# POWER_GEN.net
KiCad netlist of a schematic drawn in Altium Designer
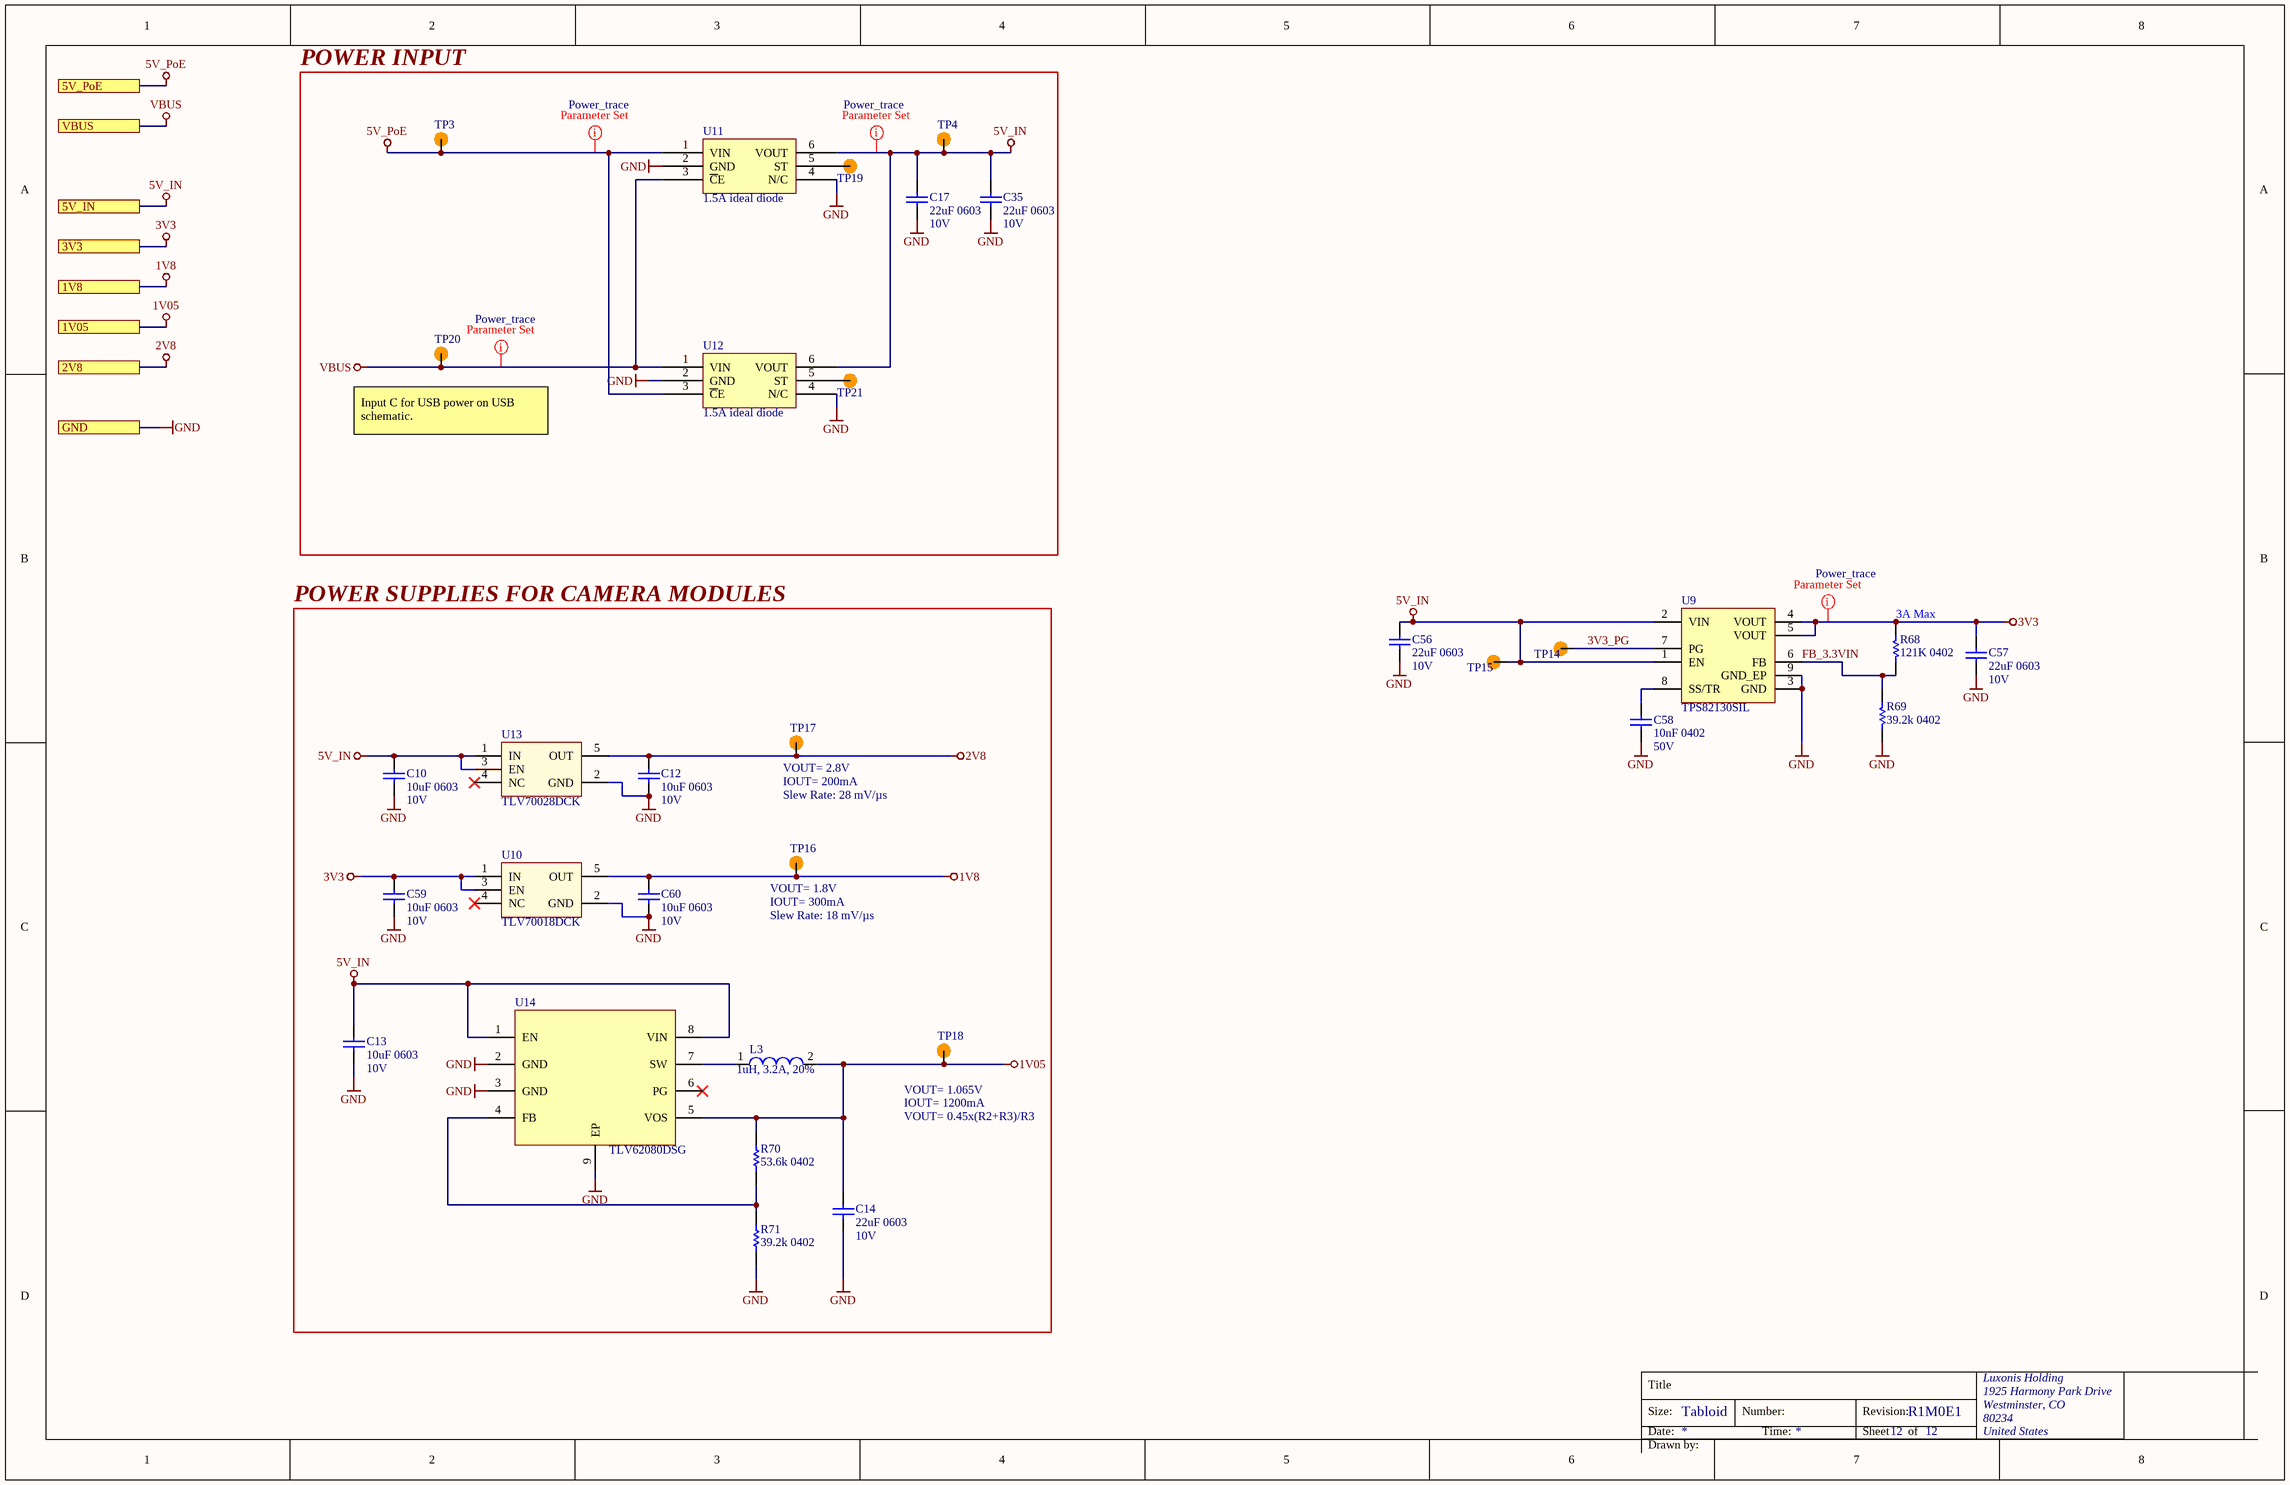
[diagram p0: POWER_GEN.SchDoc]

(export (version "E")
  (design (tool "Eeschema 10.0.6"))
  (components
    (comp (ref "C10")
      (value "10uF 0603")
      (footprint "CAP_Altium_Vault_Generic:CAPC0603(1608)100_N")
      (description "CAP CER 10UF 10V X5R 0603 20%")
      (fields (field (name "TOLERANCE") "20%") (field (name "VOLTAGE RATING") "10V"))
      (libsource (lib "LuxonisMaster") (part "GRM188R61A106ME69D"))
    )
    (comp (ref "C12")
      (value "10uF 0603")
      (footprint "CAP_Altium_Vault_Generic:CAPC0603(1608)100_N")
      (description "CAP CER 10UF 10V X5R 0603 20%")
      (fields (field (name "TOLERANCE") "20%") (field (name "VOLTAGE RATING") "10V"))
      (libsource (lib "LuxonisMaster") (part "GRM188R61A106ME69D"))
    )
    (comp (ref "C13")
      (value "10uF 0603")
      (footprint "CAP_Altium_Vault_Generic:CAPC0603(1608)100_L")
      (description "CAP CER 10UF 10V X5R 0603 20%")
      (fields (field (name "TOLERANCE") "20%") (field (name "VOLTAGE RATING") "10V"))
      (libsource (lib "LuxonisMaster") (part "GRM188R61A106ME69D"))
    )
    (comp (ref "C14")
      (value "22uF 0603")
      (footprint "CAP_Altium_Vault_Generic:CAPC0603(1608)100_L")
      (description "CAP CER 22UF 10V X5R 0603 20%")
      (fields (field (name "TOLERANCE") "20%") (field (name "VOLTAGE RATING") "10V"))
      (libsource (lib "LuxonisMaster") (part "GRM188R61A226ME15D"))
    )
    (comp (ref "C17")
      (value "22uF 0603")
      (footprint "CAP_Altium_Vault_Generic:CAPC0603(1608)100_L")
      (description "CAP CER 22UF 10V X5R 0603 20%")
      (fields (field (name "TOLERANCE") "20%") (field (name "VOLTAGE RATING") "10V"))
      (libsource (lib "LuxonisMaster") (part "GRM188R61A226ME15D"))
    )
    (comp (ref "C35")
      (value "22uF 0603")
      (footprint "CAP_Altium_Vault_Generic:CAPC0603(1608)100_L")
      (description "CAP CER 22UF 10V X5R 0603 20%")
      (fields (field (name "TOLERANCE") "20%") (field (name "VOLTAGE RATING") "10V"))
      (libsource (lib "LuxonisMaster") (part "GRM188R61A226ME15D"))
    )
    (comp (ref "C56")
      (value "22uF 0603")
      (footprint "CAP_Altium_Vault_Generic:CAPC0603(1608)100_N")
      (description "CAP CER 22UF 10V X5R 0603 20%")
      (fields (field (name "TOLERANCE") "20%") (field (name "VOLTAGE RATING") "10V"))
      (libsource (lib "LuxonisMaster") (part "GRM188R61A226ME15D"))
    )
    (comp (ref "C57")
      (value "22uF 0603")
      (footprint "CAP_Altium_Vault_Generic:CAPC0603(1608)100_N")
      (description "CAP CER 22UF 10V X5R 0603 20%")
      (fields (field (name "TOLERANCE") "20%") (field (name "VOLTAGE RATING") "10V"))
      (libsource (lib "LuxonisMaster") (part "GRM188R61A226ME15D"))
    )
    (comp (ref "C58")
      (value "10nF 0402")
      (footprint "CAP_Altium_Vault_Generic:CAPC0402(1005)60_N")
      (description "CAP CER 10000PF 50V X7R 0402")
      (fields
        (field (name "TOLERANCE") "10%")
        (field (name "VOLTAGE") "25V")
        (field (name "VOLTAGE RATING") "50V")
      )
      (libsource (lib "LuxonisMaster") (part "GRM155R71H103KA88D"))
    )
    (comp (ref "C59")
      (value "10uF 0603")
      (footprint "CAP_Altium_Vault_Generic:CAPC0603(1608)100_N")
      (description "CAP CER 10UF 10V X5R 0603 20%")
      (fields (field (name "TOLERANCE") "20%") (field (name "VOLTAGE RATING") "10V"))
      (libsource (lib "LuxonisMaster") (part "GRM188R61A106ME69D"))
    )
    (comp (ref "C60")
      (value "10uF 0603")
      (footprint "CAP_Altium_Vault_Generic:CAPC0603(1608)100_N")
      (description "CAP CER 10UF 10V X5R 0603 20%")
      (fields (field (name "TOLERANCE") "20%") (field (name "VOLTAGE RATING") "10V"))
      (libsource (lib "LuxonisMaster") (part "GRM188R61A106ME69D"))
    )
    (comp (ref "L3")
      (value "1uH, 3.2A, 20%")
      (footprint "LuxonisMaster:DFE252012P-1R0M=P2")
      (description "FIXED IND 1UH 3.2A 42 MOHM SMD")
      (fields
        (field (name "MANUFACTURER") "Murata")
        (field (name "MANUFACTURER PART NUMBER") "DFE252012P-1R0M=P2")
      )
      (libsource (lib "LuxonisMaster") (part "DFE252012P-1R0M=P2"))
    )
    (comp (ref "R68")
      (value "121K 0402")
      (footprint "RES_Altium_Vault_Generic:RESC0402(1005)_N")
      (description "RES SMD 121K OHM 1% 1/16W 0402")
      (fields (field (name "TOLERANCE") "1%"))
      (libsource (lib "LuxonisMaster") (part "RC0402FR-07121KL"))
    )
    (comp (ref "R69")
      (value "39.2k 0402")
      (footprint "RES_Altium_Vault_Generic:RESC0402(1005)_N")
      (description "RES SMD 39.2K OHM 1% 1/16W 0402")
      (fields (field (name "TOLERANCE") "1%"))
      (libsource (lib "LuxonisMaster") (part "CRCW040239K2FKED"))
    )
    (comp (ref "R70")
      (value "53.6k 0402")
      (footprint "RES_Altium_Vault_Generic:RESC0402(1005)_L")
      (description "RES SMD 53.6K OHM 1% 1/16W 0402")
      (fields (field (name "TOLERANCE") "1%"))
      (libsource (lib "LuxonisMaster") (part "CRCW040253K6FKED"))
    )
    (comp (ref "R71")
      (value "39.2k 0402")
      (footprint "RES_Altium_Vault_Generic:RESC0402(1005)_L")
      (description "RES SMD 39.2K OHM 1% 1/16W 0402")
      (fields (field (name "TOLERANCE") "1%"))
      (libsource (lib "LuxonisMaster") (part "CRCW040239K2FKED"))
    )
    (comp (ref "TP3")
      (value "TP100_200_NS")
      (footprint "LuxonisMaster:TP100_200_NS")
      (libsource (lib "LuxonisMaster") (part "TEST_POINT"))
    )
    (comp (ref "TP4")
      (value "TP100_200_NS")
      (footprint "LuxonisMaster:TP100_200_NS")
      (libsource (lib "LuxonisMaster") (part "TEST_POINT"))
    )
    (comp (ref "TP14")
      (value "TP100_200_NS")
      (footprint "LuxonisMaster:TP100_200_NS")
      (libsource (lib "LuxonisMaster") (part "TEST_POINT"))
    )
    (comp (ref "TP15")
      (value "TP100_200_NS")
      (footprint "LuxonisMaster:TP100_200_NS")
      (libsource (lib "LuxonisMaster") (part "TEST_POINT"))
    )
    (comp (ref "TP16")
      (value "TP100_200_NS")
      (footprint "LuxonisMaster:TP100_200_NS")
      (libsource (lib "LuxonisMaster") (part "TEST_POINT"))
    )
    (comp (ref "TP17")
      (value "TP100_200_NS")
      (footprint "LuxonisMaster:TP100_200_NS")
      (libsource (lib "LuxonisMaster") (part "TEST_POINT"))
    )
    (comp (ref "TP18")
      (value "TP100_200_NS")
      (footprint "LuxonisMaster:TP100_200_NS")
      (libsource (lib "LuxonisMaster") (part "TEST_POINT"))
    )
    (comp (ref "TP19")
      (value "TP100_200_NS")
      (footprint "LuxonisMaster:TP100_200_NS")
      (libsource (lib "LuxonisMaster") (part "TEST_POINT"))
    )
    (comp (ref "TP20")
      (value "TP100_200_NS")
      (footprint "LuxonisMaster:TP100_200_NS")
      (libsource (lib "LuxonisMaster") (part "TEST_POINT"))
    )
    (comp (ref "TP21")
      (value "TP100_200_NS")
      (footprint "LuxonisMaster:TP100_200_NS")
      (libsource (lib "LuxonisMaster") (part "TEST_POINT"))
    )
    (comp (ref "U9")
      (value "TPS82130SIL")
      (footprint "LuxonisMaster:TPS82130SIL")
      (description "DC DC CONVERTER 0.9-5V")
      (libsource (lib "LuxonisMaster") (part "TPS82130SIL"))
    )
    (comp (ref "U10")
      (value "TLV70018DCK")
      (footprint "LuxonisMaster:TLV70018DCK")
      (description "IC REG LINEAR 1.8V 200MA SC70-5 Linear Voltage Regulator IC  1 Output  200mA SC-70-5")
      (libsource (lib "LuxonisMaster") (part "TLV70018DCK"))
    )
    (comp (ref "U11")
      (value "1.5A ideal diode")
      (footprint "LuxonisMaster:LM66100DCKR")
      (description "IC OR CTRLR IDEAL DIODE SC70-6")
      (libsource (lib "LuxonisMaster") (part "LM66100DCKR"))
    )
    (comp (ref "U12")
      (value "1.5A ideal diode")
      (footprint "LuxonisMaster:LM66100DCKR")
      (description "IC OR CTRLR IDEAL DIODE SC70-6")
      (libsource (lib "LuxonisMaster") (part "LM66100DCKR"))
    )
    (comp (ref "U13")
      (value "TLV70028DCK")
      (footprint "LuxonisMaster:TLV70028DCK")
      (description "IC REG LINEAR 2.8V 200MA SC70-5 Linear Voltage Regulator IC  1 Output  200mA SC-70-5")
      (libsource (lib "LuxonisMaster") (part "TLV70028DCK"))
    )
    (comp (ref "U14")
      (value "TLV62080DSG")
      (footprint "LuxonisMaster:TLV62080DSG")
      (description "IC REG BUCK ADJ 1.2A SYNC 8WSON")
      (libsource (lib "LuxonisMaster") (part "TLV62080DSG"))
    )
  )
  (nets
    (net (code "1") (name "/3V3_PG") (class "Default")
      (node (ref "TP14") (pin "1") (pintype "passive"))
      (node (ref "U9") (pin "7") (pinfunction "PG_7") (pintype "passive"))
    )
    (net (code "2") (name "/FB_3.3VIN") (class "Default")
      (node (ref "R68") (pin "2") (pinfunction "2_2") (pintype "passive"))
      (node (ref "R69") (pin "1") (pinfunction "1_1") (pintype "passive"))
      (node (ref "U9") (pin "6") (pinfunction "FB_6") (pintype "passive"))
    )
    (net (code "3") (name "1V05") (class "Default")
      (node (ref "C14") (pin "2") (pinfunction "2_2") (pintype "passive"))
      (node (ref "L3") (pin "2") (pinfunction "2_2") (pintype "passive"))
      (node (ref "R70") (pin "2") (pinfunction "2_2") (pintype "passive"))
      (node (ref "TP18") (pin "1") (pintype "passive"))
      (node (ref "U14") (pin "5") (pinfunction "VOS_5") (pintype "passive"))
    )
    (net (code "4") (name "1V8") (class "Default")
      (node (ref "C60") (pin "2") (pinfunction "2_2") (pintype "passive"))
      (node (ref "TP16") (pin "1") (pintype "passive"))
      (node (ref "U10") (pin "5") (pinfunction "OUT_5") (pintype "passive"))
    )
    (net (code "5") (name "2V8") (class "Default")
      (node (ref "C12") (pin "2") (pinfunction "2_2") (pintype "passive"))
      (node (ref "TP17") (pin "1") (pintype "passive"))
      (node (ref "U13") (pin "5") (pinfunction "OUT_5") (pintype "passive"))
    )
    (net (code "6") (name "3V3") (class "Default")
      (node (ref "C57") (pin "1") (pinfunction "1_1") (pintype "passive"))
      (node (ref "C59") (pin "2") (pinfunction "2_2") (pintype "passive"))
      (node (ref "R68") (pin "1") (pinfunction "1_1") (pintype "passive"))
      (node (ref "U10") (pin "1") (pinfunction "IN_1") (pintype "passive"))
      (node (ref "U10") (pin "3") (pinfunction "EN_3") (pintype "passive"))
      (node (ref "U9") (pin "4") (pinfunction "VOUT_4") (pintype "passive"))
      (node (ref "U9") (pin "5") (pinfunction "VOUT_5") (pintype "passive"))
    )
    (net (code "7") (name "5V_IN") (class "Default")
      (node (ref "C10") (pin "2") (pinfunction "2_2") (pintype "passive"))
      (node (ref "C13") (pin "2") (pinfunction "2_2") (pintype "passive"))
      (node (ref "C17") (pin "2") (pinfunction "2_2") (pintype "passive"))
      (node (ref "C35") (pin "2") (pinfunction "2_2") (pintype "passive"))
      (node (ref "C56") (pin "2") (pinfunction "2_2") (pintype "passive"))
      (node (ref "TP15") (pin "1") (pintype "passive"))
      (node (ref "TP4") (pin "1") (pintype "passive"))
      (node (ref "U11") (pin "6") (pinfunction "VOUT_6") (pintype "passive"))
      (node (ref "U12") (pin "6") (pinfunction "VOUT_6") (pintype "passive"))
      (node (ref "U13") (pin "1") (pinfunction "IN_1") (pintype "passive"))
      (node (ref "U13") (pin "3") (pinfunction "EN_3") (pintype "passive"))
      (node (ref "U14") (pin "1") (pinfunction "EN_1") (pintype "passive"))
      (node (ref "U14") (pin "8") (pinfunction "VIN_8") (pintype "passive"))
      (node (ref "U9") (pin "1") (pinfunction "EN_1") (pintype "passive"))
      (node (ref "U9") (pin "2") (pinfunction "VIN_2") (pintype "passive"))
    )
    (net (code "8") (name "5V_PoE") (class "Default")
      (node (ref "TP3") (pin "1") (pintype "passive"))
      (node (ref "U11") (pin "1") (pinfunction "VIN_1") (pintype "passive"))
      (node (ref "U12") (pin "3") (pinfunction "~{C}E_3") (pintype "passive"))
    )
    (net (code "9") (name "GND") (class "Default")
      (node (ref "C10") (pin "1") (pinfunction "1_1") (pintype "passive"))
      (node (ref "C12") (pin "1") (pinfunction "1_1") (pintype "passive"))
      (node (ref "C13") (pin "1") (pinfunction "1_1") (pintype "passive"))
      (node (ref "C14") (pin "1") (pinfunction "1_1") (pintype "passive"))
      (node (ref "C17") (pin "1") (pinfunction "1_1") (pintype "passive"))
      (node (ref "C35") (pin "1") (pinfunction "1_1") (pintype "passive"))
      (node (ref "C56") (pin "1") (pinfunction "1_1") (pintype "passive"))
      (node (ref "C57") (pin "2") (pinfunction "2_2") (pintype "passive"))
      (node (ref "C58") (pin "1") (pinfunction "1_1") (pintype "passive"))
      (node (ref "C59") (pin "1") (pinfunction "1_1") (pintype "passive"))
      (node (ref "C60") (pin "1") (pinfunction "1_1") (pintype "passive"))
      (node (ref "R69") (pin "2") (pinfunction "2_2") (pintype "passive"))
      (node (ref "R71") (pin "1") (pinfunction "1_1") (pintype "passive"))
      (node (ref "U10") (pin "2") (pinfunction "GND_2") (pintype "passive"))
      (node (ref "U11") (pin "2") (pinfunction "GND_2") (pintype "passive"))
      (node (ref "U11") (pin "4") (pinfunction "N/C_4") (pintype "passive"))
      (node (ref "U12") (pin "2") (pinfunction "GND_2") (pintype "passive"))
      (node (ref "U12") (pin "4") (pinfunction "N/C_4") (pintype "passive"))
      (node (ref "U13") (pin "2") (pinfunction "GND_2") (pintype "passive"))
      (node (ref "U14") (pin "2") (pinfunction "GND_2") (pintype "passive"))
      (node (ref "U14") (pin "3") (pinfunction "GND_3") (pintype "passive"))
      (node (ref "U14") (pin "9") (pinfunction "EP_9") (pintype "passive"))
      (node (ref "U9") (pin "3") (pinfunction "GND_3") (pintype "passive"))
      (node (ref "U9") (pin "9") (pinfunction "GND_EP_9") (pintype "passive"))
    )
    (net (code "10") (name "Net-(U9-SS{slash}TR)") (class "Default")
      (node (ref "C58") (pin "2") (pinfunction "2_2") (pintype "passive"))
      (node (ref "U9") (pin "8") (pinfunction "SS/TR_8") (pintype "passive"))
    )
    (net (code "11") (name "Net-(U11-ST)") (class "Default")
      (node (ref "TP19") (pin "1") (pintype "passive"))
      (node (ref "U11") (pin "5") (pinfunction "ST_5") (pintype "passive"))
    )
    (net (code "12") (name "Net-(U12-ST)") (class "Default")
      (node (ref "TP21") (pin "1") (pintype "passive"))
      (node (ref "U12") (pin "5") (pinfunction "ST_5") (pintype "passive"))
    )
    (net (code "13") (name "Net-(U14-FB)") (class "Default")
      (node (ref "R70") (pin "1") (pinfunction "1_1") (pintype "passive"))
      (node (ref "R71") (pin "2") (pinfunction "2_2") (pintype "passive"))
      (node (ref "U14") (pin "4") (pinfunction "FB_4") (pintype "passive"))
    )
    (net (code "14") (name "Net-(U14-SW)") (class "Default")
      (node (ref "L3") (pin "1") (pinfunction "1_1") (pintype "passive"))
      (node (ref "U14") (pin "7") (pinfunction "SW_7") (pintype "passive"))
    )
    (net (code "15") (name "VBUS") (class "Default")
      (node (ref "TP20") (pin "1") (pintype "passive"))
      (node (ref "U11") (pin "3") (pinfunction "~{C}E_3") (pintype "passive"))
      (node (ref "U12") (pin "1") (pinfunction "VIN_1") (pintype "passive"))
    )
    (net (code "16") (name "unconnected-(U10-NC-Pad4)") (class "Default")
      (node (ref "U10") (pin "4") (pinfunction "NC_4") (pintype "passive+no_connect"))
    )
    (net (code "17") (name "unconnected-(U13-NC-Pad4)") (class "Default")
      (node (ref "U13") (pin "4") (pinfunction "NC_4") (pintype "passive+no_connect"))
    )
    (net (code "18") (name "unconnected-(U14-PG-Pad6)") (class "Default")
      (node (ref "U14") (pin "6") (pinfunction "PG_6") (pintype "passive+no_connect"))
    )
  )
)
